# rel-eeprom-prog.net
KiCad netlist of a schematic drawn in EAGLE
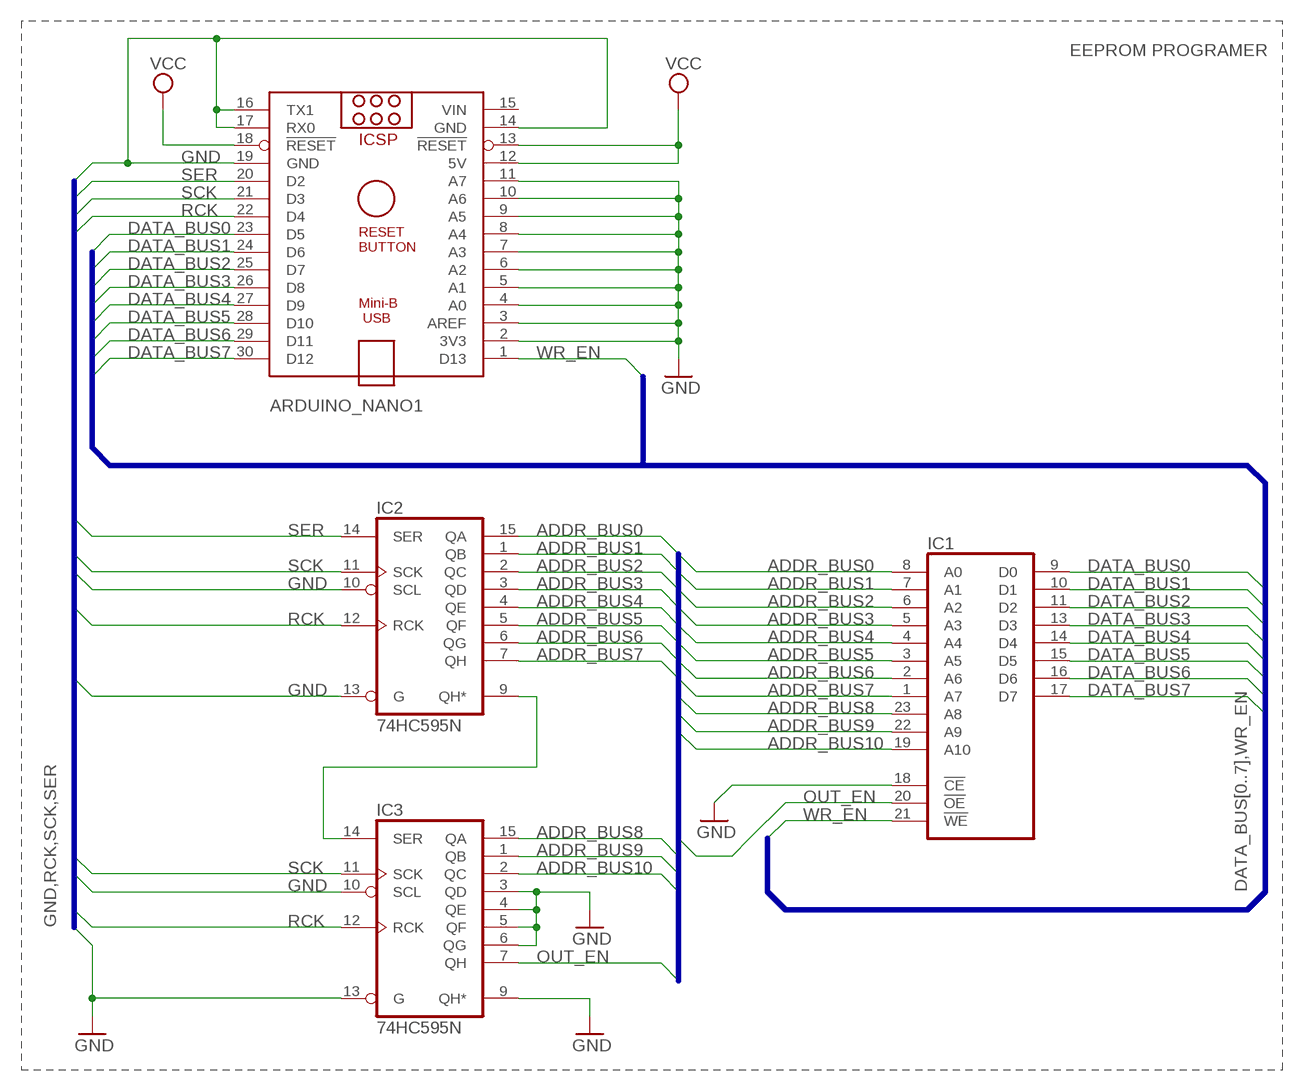
[diagram p0: schematic, sheet 1]

(export (version "E")
  (design (tool "Eeschema 10.0.6"))
  (components
    (comp (ref "ARDUINO_NANO1")
      (value "ARDUINO_NANO")
      (footprint "eagle-import:ARDUINO_NANO")
      (libsource (lib "eagle-import") (part "ARDUINO_NANO"))
    )
    (comp (ref "IC1")
      (value "2816")
      (footprint "eagle-import:DIL24")
      (libsource (lib "eagle-import") (part "2816"))
    )
    (comp (ref "IC2")
      (value "74HC595N")
      (footprint "eagle-import:DIL16")
      (libsource (lib "eagle-import") (part "74595NHC"))
    )
    (comp (ref "IC3")
      (value "74HC595N")
      (footprint "eagle-import:DIL16")
      (libsource (lib "eagle-import") (part "74595NHC"))
    )
  )
  (nets
    (net (code "1") (name "/ADDR_BUS0") (class "Default")
      (node (ref "IC1") (pin "8") (pinfunction "A0_8") (pintype "input"))
      (node (ref "IC2") (pin "15") (pinfunction "QA_15") (pintype "tri_state"))
    )
    (net (code "2") (name "/ADDR_BUS1") (class "Default")
      (node (ref "IC1") (pin "7") (pinfunction "A1_7") (pintype "input"))
      (node (ref "IC2") (pin "1") (pinfunction "QB_1") (pintype "tri_state"))
    )
    (net (code "3") (name "/ADDR_BUS2") (class "Default")
      (node (ref "IC1") (pin "6") (pinfunction "A2_6") (pintype "input"))
      (node (ref "IC2") (pin "2") (pinfunction "QC_2") (pintype "tri_state"))
    )
    (net (code "4") (name "/ADDR_BUS3") (class "Default")
      (node (ref "IC1") (pin "5") (pinfunction "A3_5") (pintype "input"))
      (node (ref "IC2") (pin "3") (pinfunction "QD_3") (pintype "tri_state"))
    )
    (net (code "5") (name "/ADDR_BUS4") (class "Default")
      (node (ref "IC1") (pin "4") (pinfunction "A4_4") (pintype "input"))
      (node (ref "IC2") (pin "4") (pinfunction "QE_4") (pintype "tri_state"))
    )
    (net (code "6") (name "/ADDR_BUS5") (class "Default")
      (node (ref "IC1") (pin "3") (pinfunction "A5_3") (pintype "input"))
      (node (ref "IC2") (pin "5") (pinfunction "QF_5") (pintype "tri_state"))
    )
    (net (code "7") (name "/ADDR_BUS6") (class "Default")
      (node (ref "IC1") (pin "2") (pinfunction "A6_2") (pintype "input"))
      (node (ref "IC2") (pin "6") (pinfunction "QG_6") (pintype "tri_state"))
    )
    (net (code "8") (name "/ADDR_BUS7") (class "Default")
      (node (ref "IC1") (pin "1") (pinfunction "A7_1") (pintype "input"))
      (node (ref "IC2") (pin "7") (pinfunction "QH_7") (pintype "tri_state"))
    )
    (net (code "9") (name "/ADDR_BUS8") (class "Default")
      (node (ref "IC1") (pin "23") (pinfunction "A8_23") (pintype "input"))
      (node (ref "IC3") (pin "15") (pinfunction "QA_15") (pintype "tri_state"))
    )
    (net (code "10") (name "/ADDR_BUS9") (class "Default")
      (node (ref "IC1") (pin "22") (pinfunction "A9_22") (pintype "input"))
      (node (ref "IC3") (pin "1") (pinfunction "QB_1") (pintype "tri_state"))
    )
    (net (code "11") (name "/ADDR_BUS10") (class "Default")
      (node (ref "IC1") (pin "19") (pinfunction "A10_19") (pintype "input"))
      (node (ref "IC3") (pin "2") (pinfunction "QC_2") (pintype "tri_state"))
    )
    (net (code "12") (name "/DATA_BUS0") (class "Default")
      (node (ref "ARDUINO_NANO1") (pin "23") (pinfunction "D5_23") (pintype "bidirectional"))
      (node (ref "IC1") (pin "9") (pinfunction "D0_9") (pintype "bidirectional"))
    )
    (net (code "13") (name "/DATA_BUS1") (class "Default")
      (node (ref "ARDUINO_NANO1") (pin "24") (pinfunction "D6_24") (pintype "bidirectional"))
      (node (ref "IC1") (pin "10") (pinfunction "D1_10") (pintype "bidirectional"))
    )
    (net (code "14") (name "/DATA_BUS2") (class "Default")
      (node (ref "ARDUINO_NANO1") (pin "25") (pinfunction "D7_25") (pintype "bidirectional"))
      (node (ref "IC1") (pin "11") (pinfunction "D2_11") (pintype "bidirectional"))
    )
    (net (code "15") (name "/DATA_BUS3") (class "Default")
      (node (ref "ARDUINO_NANO1") (pin "26") (pinfunction "D8_26") (pintype "bidirectional"))
      (node (ref "IC1") (pin "13") (pinfunction "D3_13") (pintype "bidirectional"))
    )
    (net (code "16") (name "/DATA_BUS4") (class "Default")
      (node (ref "ARDUINO_NANO1") (pin "27") (pinfunction "D9_27") (pintype "bidirectional"))
      (node (ref "IC1") (pin "14") (pinfunction "D4_14") (pintype "bidirectional"))
    )
    (net (code "17") (name "/DATA_BUS5") (class "Default")
      (node (ref "ARDUINO_NANO1") (pin "28") (pinfunction "D10_28") (pintype "bidirectional"))
      (node (ref "IC1") (pin "15") (pinfunction "D5_15") (pintype "bidirectional"))
    )
    (net (code "18") (name "/DATA_BUS6") (class "Default")
      (node (ref "ARDUINO_NANO1") (pin "29") (pinfunction "D11_29") (pintype "bidirectional"))
      (node (ref "IC1") (pin "16") (pinfunction "D6_16") (pintype "bidirectional"))
    )
    (net (code "19") (name "/DATA_BUS7") (class "Default")
      (node (ref "ARDUINO_NANO1") (pin "30") (pinfunction "D12_30") (pintype "bidirectional"))
      (node (ref "IC1") (pin "17") (pinfunction "D7_17") (pintype "bidirectional"))
    )
    (net (code "20") (name "/OUT_EN") (class "Default")
      (node (ref "IC1") (pin "20") (pinfunction "~{OE}_20") (pintype "input"))
      (node (ref "IC3") (pin "7") (pinfunction "QH_7") (pintype "tri_state"))
    )
    (net (code "21") (name "/RCK") (class "Default")
      (node (ref "ARDUINO_NANO1") (pin "22") (pinfunction "D4_22") (pintype "bidirectional"))
      (node (ref "IC2") (pin "12") (pinfunction "RCK_12") (pintype "input"))
      (node (ref "IC3") (pin "12") (pinfunction "RCK_12") (pintype "input"))
    )
    (net (code "22") (name "/SCK") (class "Default")
      (node (ref "ARDUINO_NANO1") (pin "21") (pinfunction "D3_21") (pintype "bidirectional"))
      (node (ref "IC2") (pin "11") (pinfunction "SCK_11") (pintype "input"))
      (node (ref "IC3") (pin "11") (pinfunction "SCK_11") (pintype "input"))
    )
    (net (code "23") (name "/SER") (class "Default")
      (node (ref "ARDUINO_NANO1") (pin "20") (pinfunction "D2_20") (pintype "bidirectional"))
      (node (ref "IC2") (pin "14") (pinfunction "SER_14") (pintype "input"))
    )
    (net (code "24") (name "/VIN") (class "Default")
      (node (ref "ARDUINO_NANO1") (pin "15") (pinfunction "VIN_15") (pintype "power_in"))
    )
    (net (code "25") (name "/WR_EN") (class "Default")
      (node (ref "ARDUINO_NANO1") (pin "1") (pinfunction "D13_1") (pintype "bidirectional"))
      (node (ref "IC1") (pin "21") (pinfunction "~{WE}_21") (pintype "input"))
    )
    (net (code "28") (name "GND") (class "Default")
      (node (ref "ARDUINO_NANO1") (pin "10") (pinfunction "A6_10") (pintype "bidirectional"))
      (node (ref "ARDUINO_NANO1") (pin "11") (pinfunction "A7_11") (pintype "bidirectional"))
      (node (ref "ARDUINO_NANO1") (pin "14") (pinfunction "GND_14") (pintype "power_in"))
      (node (ref "ARDUINO_NANO1") (pin "16") (pinfunction "TX1_16") (pintype "bidirectional"))
      (node (ref "ARDUINO_NANO1") (pin "17") (pinfunction "RX0_17") (pintype "bidirectional"))
      (node (ref "ARDUINO_NANO1") (pin "19") (pinfunction "GND_19") (pintype "power_in"))
      (node (ref "ARDUINO_NANO1") (pin "2") (pinfunction "3V3_2") (pintype "output"))
      (node (ref "ARDUINO_NANO1") (pin "3") (pinfunction "AREF_3") (pintype "input"))
      (node (ref "ARDUINO_NANO1") (pin "4") (pinfunction "A0_4") (pintype "bidirectional"))
      (node (ref "ARDUINO_NANO1") (pin "5") (pinfunction "A1_5") (pintype "bidirectional"))
      (node (ref "ARDUINO_NANO1") (pin "6") (pinfunction "A2_6") (pintype "bidirectional"))
      (node (ref "ARDUINO_NANO1") (pin "7") (pinfunction "A3_7") (pintype "bidirectional"))
      (node (ref "ARDUINO_NANO1") (pin "8") (pinfunction "A4_8") (pintype "bidirectional"))
      (node (ref "ARDUINO_NANO1") (pin "9") (pinfunction "A5_9") (pintype "bidirectional"))
      (node (ref "IC1") (pin "18") (pinfunction "~{CE}_18") (pintype "input"))
      (node (ref "IC2") (pin "10") (pinfunction "SCL_10") (pintype "input"))
      (node (ref "IC2") (pin "13") (pinfunction "G_13") (pintype "input"))
      (node (ref "IC3") (pin "10") (pinfunction "SCL_10") (pintype "input"))
      (node (ref "IC3") (pin "13") (pinfunction "G_13") (pintype "input"))
      (node (ref "IC3") (pin "3") (pinfunction "QD_3") (pintype "tri_state"))
      (node (ref "IC3") (pin "4") (pinfunction "QE_4") (pintype "tri_state"))
      (node (ref "IC3") (pin "5") (pinfunction "QF_5") (pintype "tri_state"))
      (node (ref "IC3") (pin "6") (pinfunction "QG_6") (pintype "tri_state"))
      (node (ref "IC3") (pin "9") (pinfunction "QH*_9") (pintype "tri_state"))
    )
    (net (code "29") (name "Net-(IC2A-QH*)") (class "Default")
      (node (ref "IC2") (pin "9") (pinfunction "QH*_9") (pintype "tri_state"))
      (node (ref "IC3") (pin "14") (pinfunction "SER_14") (pintype "input"))
    )
    (net (code "30") (name "VCC") (class "Default")
      (node (ref "ARDUINO_NANO1") (pin "12") (pinfunction "5V_12") (pintype "power_in"))
      (node (ref "ARDUINO_NANO1") (pin "13") (pinfunction "~{RESET}_13") (pintype "input"))
      (node (ref "ARDUINO_NANO1") (pin "18") (pinfunction "~{RESET}_18") (pintype "input"))
    )
  )
)
